# C64_PSU_Combi.net
KiCad netlist of a schematic drawn in EAGLE
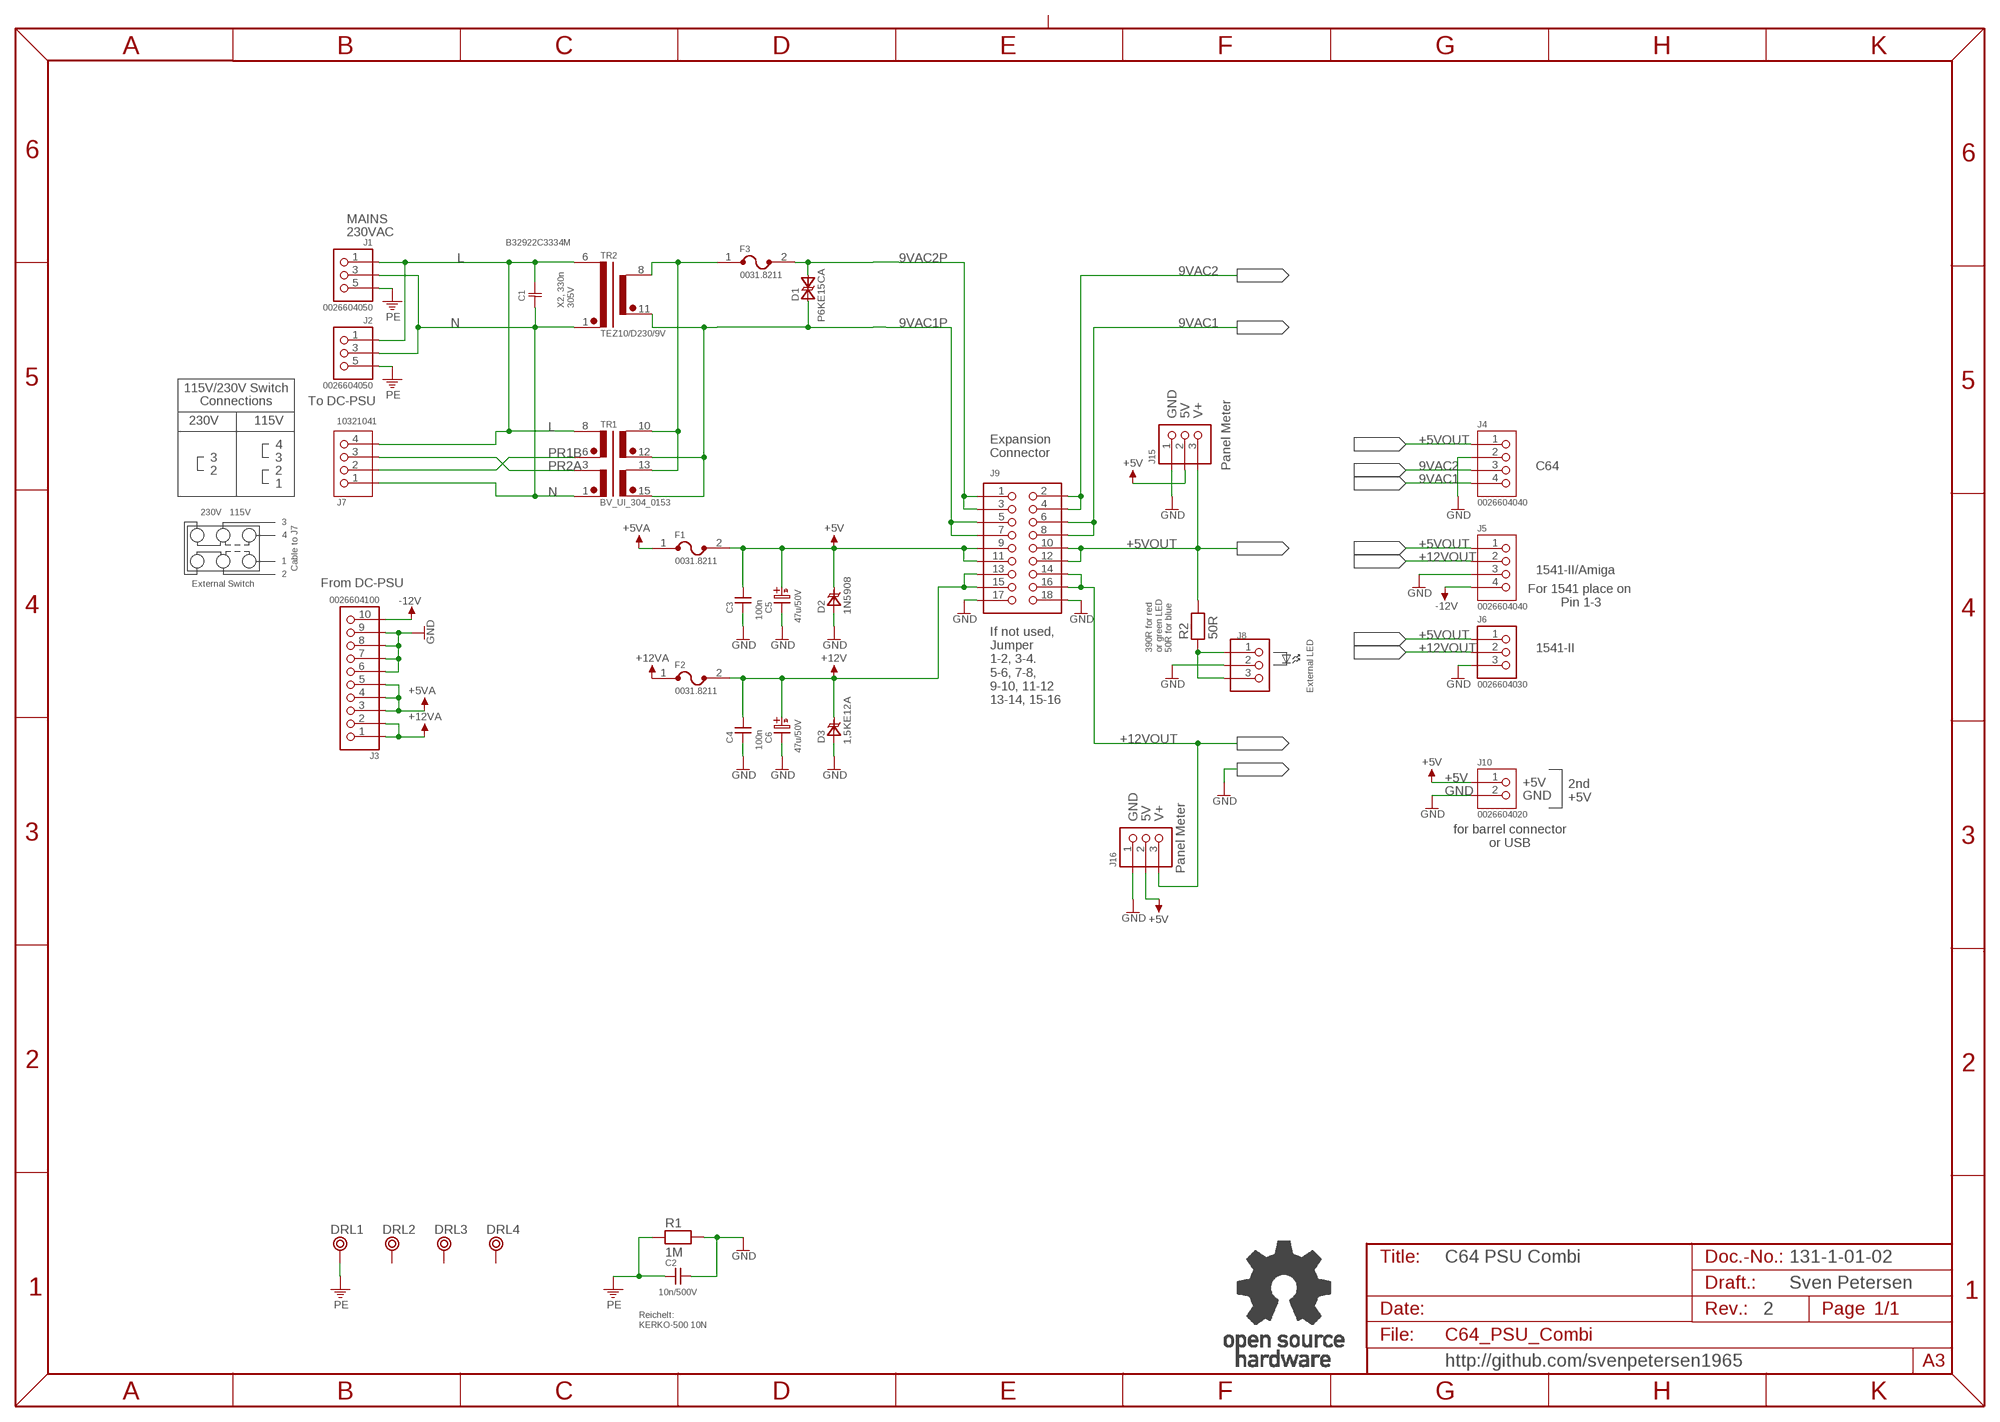
[diagram p0: schematic, sheet 1]

(export (version "E")
  (design (tool "Eeschema 10.0.6"))
  (components
    (comp (ref "C1")
      (value "B32922C3334M")
      (footprint "eagle-import:C-18X8-RM15")
      (libsource (lib "eagle-import") (part "X2--RM15-18X8"))
    )
    (comp (ref "C2")
      (value "10n/500V")
      (footprint "eagle-import:C-5")
      (libsource (lib "eagle-import") (part "CAP02"))
    )
    (comp (ref "C3")
      (value "100n")
      (footprint "eagle-import:C-2,5")
      (libsource (lib "eagle-import") (part "CAP01"))
    )
    (comp (ref "C4")
      (value "100n")
      (footprint "eagle-import:C-2,5")
      (libsource (lib "eagle-import") (part "CAP01"))
    )
    (comp (ref "C5")
      (value "47u/50V")
      (footprint "eagle-import:C07_2,5")
      (libsource (lib "eagle-import") (part "C07/2,5"))
    )
    (comp (ref "C6")
      (value "47u/50V")
      (footprint "eagle-import:C07_2,5")
      (libsource (lib "eagle-import") (part "C07/2,5"))
    )
    (comp (ref "D1")
      (value "P6KE15CA")
      (footprint "eagle-import:CB417NP")
      (libsource (lib "eagle-import") (part "P6KE15CA"))
    )
    (comp (ref "D2")
      (value "1N5908")
      (footprint "eagle-import:CB429")
      (libsource (lib "eagle-import") (part "1N5908"))
    )
    (comp (ref "D3")
      (value "1,5KE12A")
      (footprint "eagle-import:DO-201")
      (libsource (lib "eagle-import") (part "1,5KE12A"))
    )
    (comp (ref "DRL1")
      (value "BOHR3,5OR")
      (footprint "eagle-import:BOHR3,5_OHNE_RESTRICT")
      (libsource (lib "eagle-import") (part "BOHR3,5OR"))
    )
    (comp (ref "DRL2")
      (value "BOHR3,5")
      (footprint "eagle-import:BOHR3,5")
      (libsource (lib "eagle-import") (part "BOHR3,5"))
    )
    (comp (ref "DRL3")
      (value "BOHR3,5")
      (footprint "eagle-import:BOHR3,5")
      (libsource (lib "eagle-import") (part "BOHR3,5"))
    )
    (comp (ref "DRL4")
      (value "BOHR3,5")
      (footprint "eagle-import:BOHR3,5")
      (libsource (lib "eagle-import") (part "BOHR3,5"))
    )
    (comp (ref "F1")
      (value "0031.8211")
      (footprint "eagle-import:0031.8211")
      (libsource (lib "eagle-import") (part "0031.8211"))
    )
    (comp (ref "F2")
      (value "0031.8211")
      (footprint "eagle-import:0031.8211")
      (libsource (lib "eagle-import") (part "0031.8211"))
    )
    (comp (ref "F3")
      (value "0031.8211")
      (footprint "eagle-import:0031.8211")
      (libsource (lib "eagle-import") (part "0031.8211"))
    )
    (comp (ref "J1")
      (value "0026604050")
      (footprint "eagle-import:SPOX_3.96_5P3")
      (libsource (lib "eagle-import") (part "0026604050MOD"))
    )
    (comp (ref "J2")
      (value "0026604050")
      (footprint "eagle-import:SPOX_3.96_5P3")
      (libsource (lib "eagle-import") (part "0026604050MOD"))
    )
    (comp (ref "J3")
      (value "0026604100")
      (footprint "eagle-import:SPOX_3.96_10P")
      (libsource (lib "eagle-import") (part "0026604100"))
    )
    (comp (ref "J4")
      (value "0026604040")
      (footprint "eagle-import:SPOX_3.96_4P")
      (libsource (lib "eagle-import") (part "0026604040"))
    )
    (comp (ref "J5")
      (value "0026604040")
      (footprint "eagle-import:SPOX_3.96_4P")
      (libsource (lib "eagle-import") (part "0026604040"))
    )
    (comp (ref "J6")
      (value "0026604030")
      (footprint "eagle-import:SPOX_3.96_3P")
      (libsource (lib "eagle-import") (part "0026604030"))
    )
    (comp (ref "J7")
      (value "10321041")
      (footprint "eagle-import:SPOX_5.08_4P")
      (libsource (lib "eagle-import") (part "10321041"))
    )
    (comp (ref "J8")
      (value "PINHD-1X3")
      (footprint "eagle-import:1X03")
      (libsource (lib "eagle-import") (part "PINHD-1X3"))
    )
    (comp (ref "J9")
      (value "COMBI-9X2P")
      (footprint "eagle-import:COMBI-9X2")
      (libsource (lib "eagle-import") (part "COMBI-9X2P"))
    )
    (comp (ref "J10")
      (value "0026604020")
      (footprint "eagle-import:SPOX_3.96_2P")
      (libsource (lib "eagle-import") (part "0026604020"))
    )
    (comp (ref "J15")
      (value "6410-3P")
      (footprint "eagle-import:6410-3P")
      (libsource (lib "eagle-import") (part "6410-3P"))
    )
    (comp (ref "J16")
      (value "6410-3P")
      (footprint "eagle-import:6410-3P")
      (libsource (lib "eagle-import") (part "6410-3P"))
    )
    (comp (ref "R1")
      (value "1M")
      (footprint "eagle-import:R-10")
      (libsource (lib "eagle-import") (part "RES04"))
    )
    (comp (ref "R2")
      (value "50R")
      (footprint "eagle-import:R-10")
      (libsource (lib "eagle-import") (part "RES04"))
    )
    (comp (ref "TR1")
      (value "BV_UI_304_0153")
      (footprint "eagle-import:UI30")
      (libsource (lib "eagle-import") (part "BV_UI_304_0153"))
    )
    (comp (ref "TR2")
      (value "TEZ10/D230/9V")
      (footprint "eagle-import:TEZ10")
      (libsource (lib "eagle-import") (part "TEZ10/D230/9V"))
    )
    (comp (ref "U$31")
      (value "OPEN_SOURCE_HW")
      (footprint "eagle-import:OPENHW")
      (libsource (lib "eagle-import") (part "OPEN_SOURCE_HW"))
    )
  )
  (nets
    (net (code "1") (name "+5V") (class "Default")
      (node (ref "C3") (pin "2") (pinfunction "2_2") (pintype "passive"))
      (node (ref "C5") (pin "A") (pinfunction "+_A") (pintype "passive"))
      (node (ref "D2") (pin "K") (pinfunction "K_K") (pintype "passive"))
      (node (ref "F1") (pin "2") (pinfunction "2_2") (pintype "passive"))
      (node (ref "J10") (pin "1") (pinfunction "1_1") (pintype "passive"))
      (node (ref "J15") (pin "2") (pinfunction "2_2") (pintype "passive"))
      (node (ref "J16") (pin "2") (pinfunction "2_2") (pintype "passive"))
      (node (ref "J9") (pin "11") (pinfunction "11_11") (pintype "passive"))
      (node (ref "J9") (pin "9") (pinfunction "9_9") (pintype "passive"))
    )
    (net (code "2") (name "+5VA") (class "Default")
      (node (ref "F1") (pin "1") (pinfunction "1_1") (pintype "passive"))
      (node (ref "J3") (pin "3") (pinfunction "3_3") (pintype "passive"))
      (node (ref "J3") (pin "4") (pinfunction "4_4") (pintype "passive"))
      (node (ref "J3") (pin "5") (pinfunction "5_5") (pintype "passive"))
    )
    (net (code "3") (name "+12V") (class "Default")
      (node (ref "C4") (pin "2") (pinfunction "2_2") (pintype "passive"))
      (node (ref "C6") (pin "A") (pinfunction "+_A") (pintype "passive"))
      (node (ref "D3") (pin "K") (pinfunction "K_K") (pintype "passive"))
      (node (ref "F2") (pin "2") (pinfunction "2_2") (pintype "passive"))
      (node (ref "J9") (pin "13") (pinfunction "13_13") (pintype "passive"))
      (node (ref "J9") (pin "15") (pinfunction "15_15") (pintype "passive"))
    )
    (net (code "4") (name "+12VA") (class "Default")
      (node (ref "F2") (pin "1") (pinfunction "1_1") (pintype "passive"))
      (node (ref "J3") (pin "1") (pinfunction "1_1") (pintype "passive"))
      (node (ref "J3") (pin "2") (pinfunction "2_2") (pintype "passive"))
    )
    (net (code "5") (name "-12V") (class "Default")
      (node (ref "J3") (pin "10") (pinfunction "10_10") (pintype "passive"))
      (node (ref "J5") (pin "4") (pinfunction "4_4") (pintype "passive"))
    )
    (net (code "6") (name "/+5VOUT") (class "Default")
      (node (ref "J15") (pin "3") (pinfunction "3_3") (pintype "passive"))
      (node (ref "J4") (pin "1") (pinfunction "1_1") (pintype "passive"))
      (node (ref "J5") (pin "1") (pinfunction "1_1") (pintype "passive"))
      (node (ref "J6") (pin "1") (pinfunction "1_1") (pintype "passive"))
      (node (ref "J9") (pin "10") (pinfunction "10_10") (pintype "passive"))
      (node (ref "J9") (pin "12") (pinfunction "12_12") (pintype "passive"))
      (node (ref "R2") (pin "2") (pinfunction "2_2") (pintype "passive"))
    )
    (net (code "7") (name "/+12VOUT") (class "Default")
      (node (ref "J16") (pin "3") (pinfunction "3_3") (pintype "passive"))
      (node (ref "J5") (pin "2") (pinfunction "2_2") (pintype "passive"))
      (node (ref "J6") (pin "2") (pinfunction "2_2") (pintype "passive"))
      (node (ref "J9") (pin "14") (pinfunction "14_14") (pintype "passive"))
      (node (ref "J9") (pin "16") (pinfunction "16_16") (pintype "passive"))
    )
    (net (code "8") (name "/9VAC1") (class "Default")
      (node (ref "J4") (pin "4") (pinfunction "4_4") (pintype "passive"))
      (node (ref "J9") (pin "6") (pinfunction "6_6") (pintype "passive"))
      (node (ref "J9") (pin "8") (pinfunction "8_8") (pintype "passive"))
    )
    (net (code "9") (name "/9VAC1P") (class "Default")
      (node (ref "D1") (pin "A") (pinfunction "A1_A") (pintype "passive"))
      (node (ref "J9") (pin "5") (pinfunction "5_5") (pintype "passive"))
      (node (ref "J9") (pin "7") (pinfunction "7_7") (pintype "passive"))
      (node (ref "TR1") (pin "12") (pinfunction "SEC1B_12") (pintype "passive"))
      (node (ref "TR1") (pin "15") (pinfunction "SEC2B_15") (pintype "passive"))
      (node (ref "TR2") (pin "11") (pinfunction "SEC12_11") (pintype "passive"))
    )
    (net (code "10") (name "/9VAC2") (class "Default")
      (node (ref "J4") (pin "3") (pinfunction "3_3") (pintype "passive"))
      (node (ref "J9") (pin "2") (pinfunction "2_2") (pintype "passive"))
      (node (ref "J9") (pin "4") (pinfunction "4_4") (pintype "passive"))
    )
    (net (code "11") (name "/9VAC2P") (class "Default")
      (node (ref "D1") (pin "K") (pinfunction "A2_K") (pintype "passive"))
      (node (ref "F3") (pin "2") (pinfunction "2_2") (pintype "passive"))
      (node (ref "J9") (pin "1") (pinfunction "1_1") (pintype "passive"))
      (node (ref "J9") (pin "3") (pinfunction "3_3") (pintype "passive"))
    )
    (net (code "12") (name "/L") (class "Default")
      (node (ref "C1") (pin "2") (pinfunction "2_2") (pintype "passive"))
      (node (ref "J1") (pin "1") (pinfunction "1_1") (pintype "passive"))
      (node (ref "J2") (pin "1") (pinfunction "1_1") (pintype "passive"))
      (node (ref "J7") (pin "4") (pinfunction "4_4") (pintype "passive"))
      (node (ref "TR1") (pin "8") (pinfunction "PRI1A_8") (pintype "passive"))
      (node (ref "TR2") (pin "6") (pinfunction "PRI1_6") (pintype "passive"))
    )
    (net (code "13") (name "/N") (class "Default")
      (node (ref "C1") (pin "1") (pinfunction "1_1") (pintype "passive"))
      (node (ref "J1") (pin "3") (pinfunction "2_3") (pintype "passive"))
      (node (ref "J2") (pin "3") (pinfunction "2_3") (pintype "passive"))
      (node (ref "J7") (pin "1") (pinfunction "1_1") (pintype "passive"))
      (node (ref "TR1") (pin "1") (pinfunction "PRI2B_1") (pintype "passive"))
      (node (ref "TR2") (pin "1") (pinfunction "PRI2_1") (pintype "passive"))
    )
    (net (code "14") (name "/PR1B") (class "Default")
      (node (ref "J7") (pin "2") (pinfunction "2_2") (pintype "passive"))
      (node (ref "TR1") (pin "6") (pinfunction "PRI1B_6") (pintype "passive"))
    )
    (net (code "15") (name "/PR2A") (class "Default")
      (node (ref "J7") (pin "3") (pinfunction "3_3") (pintype "passive"))
      (node (ref "TR1") (pin "3") (pinfunction "PRI2A_3") (pintype "passive"))
    )
    (net (code "16") (name "GND") (class "Default")
      (node (ref "C2") (pin "2") (pinfunction "2_2") (pintype "passive"))
      (node (ref "C3") (pin "1") (pinfunction "1_1") (pintype "passive"))
      (node (ref "C4") (pin "1") (pinfunction "1_1") (pintype "passive"))
      (node (ref "C5") (pin "K") (pinfunction "-_K") (pintype "passive"))
      (node (ref "C6") (pin "K") (pinfunction "-_K") (pintype "passive"))
      (node (ref "D2") (pin "A") (pinfunction "A_A") (pintype "passive"))
      (node (ref "D3") (pin "A") (pinfunction "A_A") (pintype "passive"))
      (node (ref "J10") (pin "2") (pinfunction "2_2") (pintype "passive"))
      (node (ref "J15") (pin "1") (pinfunction "1_1") (pintype "passive"))
      (node (ref "J16") (pin "1") (pinfunction "1_1") (pintype "passive"))
      (node (ref "J3") (pin "6") (pinfunction "6_6") (pintype "passive"))
      (node (ref "J3") (pin "7") (pinfunction "7_7") (pintype "passive"))
      (node (ref "J3") (pin "8") (pinfunction "8_8") (pintype "passive"))
      (node (ref "J3") (pin "9") (pinfunction "9_9") (pintype "passive"))
      (node (ref "J4") (pin "2") (pinfunction "2_2") (pintype "passive"))
      (node (ref "J5") (pin "3") (pinfunction "3_3") (pintype "passive"))
      (node (ref "J6") (pin "3") (pinfunction "3_3") (pintype "passive"))
      (node (ref "J8") (pin "2") (pinfunction "2_2") (pintype "passive"))
      (node (ref "J9") (pin "17") (pinfunction "17_17") (pintype "passive"))
      (node (ref "J9") (pin "18") (pinfunction "18_18") (pintype "passive"))
      (node (ref "R1") (pin "2") (pinfunction "2_2") (pintype "passive"))
    )
    (net (code "17") (name "Net-(J8-Pad1)") (class "Default")
      (node (ref "J8") (pin "1") (pinfunction "1_1") (pintype "passive"))
      (node (ref "J8") (pin "3") (pinfunction "3_3") (pintype "passive"))
      (node (ref "R2") (pin "1") (pinfunction "1_1") (pintype "passive"))
    )
    (net (code "18") (name "Net-(TR1-SEC1A)") (class "Default")
      (node (ref "F3") (pin "1") (pinfunction "1_1") (pintype "passive"))
      (node (ref "TR1") (pin "10") (pinfunction "SEC1A_10") (pintype "passive"))
      (node (ref "TR1") (pin "13") (pinfunction "SEC2A_13") (pintype "passive"))
      (node (ref "TR2") (pin "8") (pinfunction "SEC11_8") (pintype "passive"))
    )
    (net (code "19") (name "PE") (class "Default")
      (node (ref "C2") (pin "1") (pinfunction "1_1") (pintype "passive"))
      (node (ref "DRL1") (pin "P$1") (pinfunction "P$1_P$1") (pintype "passive"))
      (node (ref "J1") (pin "5") (pinfunction "3_5") (pintype "passive"))
      (node (ref "J2") (pin "5") (pinfunction "3_5") (pintype "passive"))
      (node (ref "R1") (pin "1") (pinfunction "1_1") (pintype "passive"))
    )
    (net (code "20") (name "unconnected-(DRL2-PadP$1)") (class "Default")
      (node (ref "DRL2") (pin "P$1") (pinfunction "P$1_P$1") (pintype "passive"))
    )
    (net (code "21") (name "unconnected-(DRL3-PadP$1)") (class "Default")
      (node (ref "DRL3") (pin "P$1") (pinfunction "P$1_P$1") (pintype "passive"))
    )
    (net (code "22") (name "unconnected-(DRL4-PadP$1)") (class "Default")
      (node (ref "DRL4") (pin "P$1") (pinfunction "P$1_P$1") (pintype "passive"))
    )
  )
)
